# pimpleface.net
KiCad netlist of a schematic drawn in EAGLE
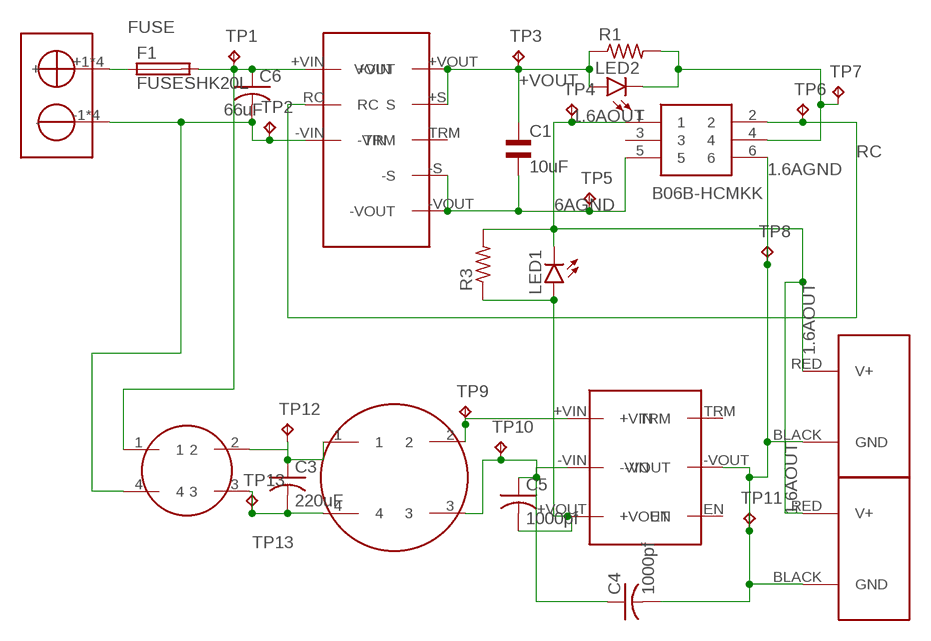
[diagram p0: schematic, sheet 1]

(export (version "E")
  (design (tool "Eeschema 10.0.6"))
  (components
    (comp (ref "BUCK150UH")
      (value "CMNMODECHOKE150UH")
      (footprint "eagle-import:CMNMODECHOKE150UH")
      (libsource (lib "eagle-import") (part "CMNMODECHOKE150UH"))
    )
    (comp (ref "C1")
      (value "10uF")
      (footprint "eagle-import:EU25-10")
      (libsource (lib "eagle-import") (part "EL-BI25-10AXIAL"))
    )
    (comp (ref "C3")
      (value "220uF")
      (footprint "eagle-import:C0805")
      (libsource (lib "eagle-import") (part "C-USC0805"))
    )
    (comp (ref "C4")
      (value "1000pf")
      (footprint "eagle-import:C0805")
      (libsource (lib "eagle-import") (part "C-USC0805"))
    )
    (comp (ref "C5")
      (value "1000pf")
      (footprint "eagle-import:C0805")
      (libsource (lib "eagle-import") (part "C-USC0805"))
    )
    (comp (ref "C6")
      (value "66uF")
      (footprint "eagle-import:C0805")
      (libsource (lib "eagle-import") (part "C-USC0805"))
    )
    (comp (ref "F1")
      (value "FUSESHK20L")
      (footprint "eagle-import:SHK20L")
      (libsource (lib "eagle-import") (part "FUSESHK20L"))
    )
    (comp (ref "J1")
      (value "B06B-HCMKK")
      (footprint "eagle-import:B06BHCMKK")
      (fields (field (name "MOUSER_PART_NUMBER") "306-B06B-HCMKK"))
      (libsource (lib "eagle-import") (part "B06B-HCMKK"))
    )
    (comp (ref "J2")
      (value "POWERPOLE_POWER45A_DRILL")
      (footprint "eagle-import:POWERPOLE_PAIR_45A_HOLE")
      (libsource (lib "eagle-import") (part "POWERPOLE_POWER45A_DRILL"))
    )
    (comp (ref "J3")
      (value "POWERPOLE_POWER45A_DRILL")
      (footprint "eagle-import:POWERPOLE_PAIR_45A_HOLE")
      (libsource (lib "eagle-import") (part "POWERPOLE_POWER45A_DRILL"))
    )
    (comp (ref "LED1")
      (value "LEDCHIP-LED0603")
      (footprint "eagle-import:CHIP-LED0603")
      (libsource (lib "eagle-import") (part "LEDCHIP-LED0603"))
    )
    (comp (ref "LED2")
      (value "LEDCHIP-LED0603")
      (footprint "eagle-import:CHIP-LED0603")
      (libsource (lib "eagle-import") (part "LEDCHIP-LED0603"))
    )
    (comp (ref "R1")
      (value "R-US_R0805")
      (footprint "eagle-import:R0805")
      (libsource (lib "eagle-import") (part "R-US_R0805"))
    )
    (comp (ref "R3")
      (value "R-US_R0805")
      (footprint "eagle-import:R0805")
      (libsource (lib "eagle-import") (part "R-US_R0805"))
    )
    (comp (ref "TP1")
      (value "TPPAD1-13")
      (footprint "eagle-import:P1-13")
      (libsource (lib "eagle-import") (part "TPPAD1-13"))
    )
    (comp (ref "TP2")
      (value "TPPAD1-13")
      (footprint "eagle-import:P1-13")
      (libsource (lib "eagle-import") (part "TPPAD1-13"))
    )
    (comp (ref "TP3")
      (value "TPPAD1-13")
      (footprint "eagle-import:P1-13")
      (libsource (lib "eagle-import") (part "TPPAD1-13"))
    )
    (comp (ref "TP4")
      (value "TPPAD1-13")
      (footprint "eagle-import:P1-13")
      (libsource (lib "eagle-import") (part "TPPAD1-13"))
    )
    (comp (ref "TP5")
      (value "TPPAD1-13")
      (footprint "eagle-import:P1-13")
      (libsource (lib "eagle-import") (part "TPPAD1-13"))
    )
    (comp (ref "TP6")
      (value "TPPAD1-13")
      (footprint "eagle-import:P1-13")
      (libsource (lib "eagle-import") (part "TPPAD1-13"))
    )
    (comp (ref "TP7")
      (value "TPPAD1-13")
      (footprint "eagle-import:P1-13")
      (libsource (lib "eagle-import") (part "TPPAD1-13"))
    )
    (comp (ref "TP8")
      (value "TPPAD1-13")
      (footprint "eagle-import:P1-13")
      (libsource (lib "eagle-import") (part "TPPAD1-13"))
    )
    (comp (ref "TP9")
      (value "TPPAD1-13")
      (footprint "eagle-import:P1-13")
      (libsource (lib "eagle-import") (part "TPPAD1-13"))
    )
    (comp (ref "TP10")
      (value "TPPAD1-13")
      (footprint "eagle-import:P1-13")
      (libsource (lib "eagle-import") (part "TPPAD1-13"))
    )
    (comp (ref "TP11")
      (value "TPPAD1-13")
      (footprint "eagle-import:P1-13")
      (libsource (lib "eagle-import") (part "TPPAD1-13"))
    )
    (comp (ref "TP12")
      (value "TPPAD1-13")
      (footprint "eagle-import:P1-13")
      (libsource (lib "eagle-import") (part "TPPAD1-13"))
    )
    (comp (ref "TP13")
      (value "TPPAD1-13")
      (footprint "eagle-import:P1-13")
      (libsource (lib "eagle-import") (part "TPPAD1-13"))
    )
    (comp (ref "U$1")
      (value "12V6ABUCKCONVERTER")
      (footprint "eagle-import:12V6ABUCKCONVERTER")
      (libsource (lib "eagle-import") (part "12V6ABUCKCONVERTER"))
    )
    (comp (ref "U$2")
      (value "SB50")
      (footprint "eagle-import:MINI-SB-50")
      (libsource (lib "eagle-import") (part "SB50"))
    )
    (comp (ref "U$3")
      (value "BUCK1.6A")
      (footprint "eagle-import:BUCK1.6A")
      (libsource (lib "eagle-import") (part "BUCK1.6A"))
    )
    (comp (ref "U$4")
      (value "CMNMODECHOKE1.2MH")
      (footprint "eagle-import:CMNMODECHOKE1.2MH")
      (libsource (lib "eagle-import") (part "CMNMODECHOKE1.2MH"))
    )
  )
  (nets
    (net (code "1") (name "/+VOUT") (class "Default")
      (node (ref "C1") (pin "1") (pinfunction "1_1") (pintype "passive"))
      (node (ref "LED2") (pin "A") (pinfunction "A_A") (pintype "passive"))
      (node (ref "R1") (pin "1") (pinfunction "1_1") (pintype "passive"))
      (node (ref "TP3") (pin "TP") (pinfunction "TP_TP") (pintype "input"))
      (node (ref "U$1") (pin "+S") (pinfunction "S_+S") (pintype "bidirectional"))
      (node (ref "U$1") (pin "+VOUT") (pinfunction "VOUT_+VOUT") (pintype "bidirectional"))
    )
    (net (code "2") (name "/1.6AGND") (class "Default")
      (node (ref "C4") (pin "2") (pinfunction "2_2") (pintype "passive"))
      (node (ref "J1") (pin "6") (pinfunction "6_6") (pintype "bidirectional"))
      (node (ref "J2") (pin "BLACK") (pinfunction "GND_BLACK") (pintype "power_in"))
      (node (ref "J3") (pin "BLACK") (pinfunction "GND_BLACK") (pintype "power_in"))
      (node (ref "TP11") (pin "TP") (pinfunction "TP_TP") (pintype "input"))
      (node (ref "TP8") (pin "TP") (pinfunction "TP_TP") (pintype "input"))
      (node (ref "U$3") (pin "-VOUT") (pinfunction "-VOUT_-VOUT") (pintype "bidirectional"))
    )
    (net (code "3") (name "/1.6AOUT") (class "Default")
      (node (ref "J1") (pin "1") (pinfunction "1_1") (pintype "bidirectional"))
      (node (ref "J2") (pin "RED") (pinfunction "V+_RED") (pintype "power_in"))
      (node (ref "J3") (pin "RED") (pinfunction "V+_RED") (pintype "power_in"))
      (node (ref "LED1") (pin "C") (pinfunction "C_C") (pintype "passive"))
      (node (ref "R3") (pin "2") (pinfunction "2_2") (pintype "passive"))
      (node (ref "TP4") (pin "TP") (pinfunction "TP_TP") (pintype "input"))
    )
    (net (code "4") (name "/6AGND") (class "Default")
      (node (ref "C1") (pin "2") (pinfunction "2_2") (pintype "passive"))
      (node (ref "J1") (pin "5") (pinfunction "5_5") (pintype "bidirectional"))
      (node (ref "TP5") (pin "TP") (pinfunction "TP_TP") (pintype "input"))
      (node (ref "U$1") (pin "-S") (pinfunction "-S_-S") (pintype "bidirectional"))
      (node (ref "U$1") (pin "-VOUT") (pinfunction "-VOUT_-VOUT") (pintype "bidirectional"))
    )
    (net (code "5") (name "/FUSE") (class "Default")
      (node (ref "F1") (pin "1A") (pinfunction "1_1A") (pintype "passive"))
      (node (ref "U$2") (pin "+1") (pinfunction "+_+1") (pintype "bidirectional"))
      (node (ref "U$2") (pin "+2") (pinfunction "+_+2") (pintype "bidirectional"))
      (node (ref "U$2") (pin "+3") (pinfunction "+_+3") (pintype "bidirectional"))
      (node (ref "U$2") (pin "+4") (pinfunction "+_+4") (pintype "bidirectional"))
    )
    (net (code "6") (name "/RC") (class "Default")
      (node (ref "J1") (pin "2") (pinfunction "2_2") (pintype "bidirectional"))
      (node (ref "TP6") (pin "TP") (pinfunction "TP_TP") (pintype "input"))
      (node (ref "U$1") (pin "RC") (pinfunction "RC_RC") (pintype "bidirectional"))
    )
    (net (code "7") (name "/TP13") (class "Default")
      (node (ref "BUCK150UH") (pin "3") (pinfunction "3_3") (pintype "bidirectional"))
      (node (ref "C3") (pin "2") (pinfunction "2_2") (pintype "passive"))
      (node (ref "TP13") (pin "TP") (pinfunction "TP_TP") (pintype "input"))
      (node (ref "U$4") (pin "4") (pinfunction "4_4") (pintype "bidirectional"))
    )
    (net (code "8") (name "Net-(BUCK150UH-Pad2)") (class "Default")
      (node (ref "BUCK150UH") (pin "2") (pinfunction "2_2") (pintype "bidirectional"))
      (node (ref "C3") (pin "1") (pinfunction "1_1") (pintype "passive"))
      (node (ref "TP12") (pin "TP") (pinfunction "TP_TP") (pintype "input"))
      (node (ref "U$4") (pin "1") (pinfunction "1_1") (pintype "bidirectional"))
    )
    (net (code "9") (name "Net-(BUCK150UH-Pad4)") (class "Default")
      (node (ref "BUCK150UH") (pin "4") (pinfunction "4_4") (pintype "bidirectional"))
      (node (ref "C6") (pin "2") (pinfunction "2_2") (pintype "passive"))
      (node (ref "TP2") (pin "TP") (pinfunction "TP_TP") (pintype "input"))
      (node (ref "U$1") (pin "-VIN") (pinfunction "-VIN_-VIN") (pintype "bidirectional"))
      (node (ref "U$2") (pin "-1") (pinfunction "-_-1") (pintype "bidirectional"))
      (node (ref "U$2") (pin "-2") (pinfunction "-_-2") (pintype "bidirectional"))
      (node (ref "U$2") (pin "-3") (pinfunction "-_-3") (pintype "bidirectional"))
      (node (ref "U$2") (pin "-4") (pinfunction "-_-4") (pintype "bidirectional"))
    )
    (net (code "10") (name "Net-(C4-Pad1)") (class "Default")
      (node (ref "C4") (pin "1") (pinfunction "1_1") (pintype "passive"))
      (node (ref "C5") (pin "1") (pinfunction "1_1") (pintype "passive"))
      (node (ref "TP10") (pin "TP") (pinfunction "TP_TP") (pintype "input"))
      (node (ref "U$3") (pin "-VIN") (pinfunction "-VIN_-VIN") (pintype "bidirectional"))
      (node (ref "U$4") (pin "3") (pinfunction "3_3") (pintype "bidirectional"))
    )
    (net (code "11") (name "Net-(C5-Pad2)") (class "Default")
      (node (ref "C5") (pin "2") (pinfunction "2_2") (pintype "passive"))
      (node (ref "LED1") (pin "A") (pinfunction "A_A") (pintype "passive"))
      (node (ref "R3") (pin "1") (pinfunction "1_1") (pintype "passive"))
      (node (ref "U$3") (pin "+VOUT") (pinfunction "+VOUT_+VOUT") (pintype "bidirectional"))
    )
    (net (code "12") (name "Net-(F1-2)") (class "Default")
      (node (ref "BUCK150UH") (pin "1") (pinfunction "1_1") (pintype "bidirectional"))
      (node (ref "C6") (pin "1") (pinfunction "1_1") (pintype "passive"))
      (node (ref "F1") (pin "2A") (pinfunction "2_2A") (pintype "passive"))
      (node (ref "TP1") (pin "TP") (pinfunction "TP_TP") (pintype "input"))
      (node (ref "U$1") (pin "+VIN") (pinfunction "+VIN_+VIN") (pintype "bidirectional"))
    )
    (net (code "13") (name "Net-(J1-Pad4)") (class "Default")
      (node (ref "J1") (pin "4") (pinfunction "4_4") (pintype "bidirectional"))
      (node (ref "LED2") (pin "C") (pinfunction "C_C") (pintype "passive"))
      (node (ref "R1") (pin "2") (pinfunction "2_2") (pintype "passive"))
      (node (ref "TP7") (pin "TP") (pinfunction "TP_TP") (pintype "input"))
    )
    (net (code "14") (name "Net-(TP9-PadTP)") (class "Default")
      (node (ref "TP9") (pin "TP") (pinfunction "TP_TP") (pintype "input"))
      (node (ref "U$3") (pin "+VIN") (pinfunction "+VIN_+VIN") (pintype "bidirectional"))
      (node (ref "U$4") (pin "2") (pinfunction "2_2") (pintype "bidirectional"))
    )
    (net (code "15") (name "unconnected-(J1-Pad3)") (class "Default")
      (node (ref "J1") (pin "3") (pinfunction "3_3") (pintype "bidirectional"))
    )
    (net (code "16") (name "unconnected-(U$1-PadTRM)") (class "Default")
      (node (ref "U$1") (pin "TRM") (pinfunction "TRM_TRM") (pintype "bidirectional"))
    )
    (net (code "17") (name "unconnected-(U$3-PadEN)") (class "Default")
      (node (ref "U$3") (pin "EN") (pinfunction "EN_EN") (pintype "bidirectional"))
    )
    (net (code "18") (name "unconnected-(U$3-PadTRM)") (class "Default")
      (node (ref "U$3") (pin "TRM") (pinfunction "TRM_TRM") (pintype "bidirectional"))
    )
  )
)
